# controller.net
KiCad netlist of a schematic drawn in EAGLE
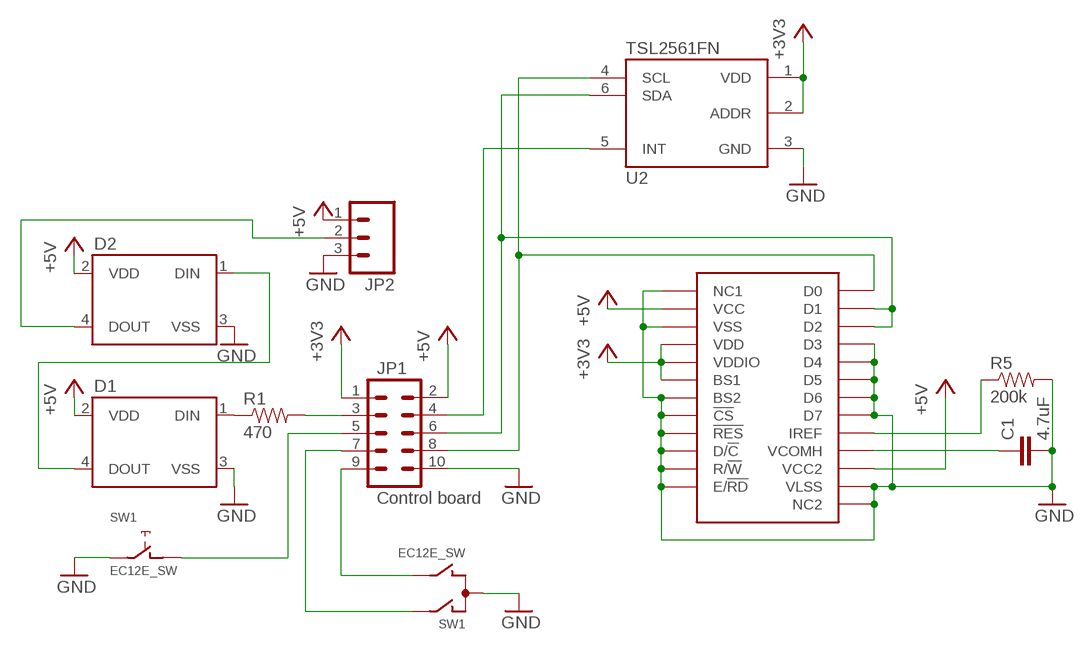
[diagram p0: schematic, sheet 1]

(export (version "E")
  (design (tool "Eeschema 10.0.6"))
  (components
    (comp (ref "C1")
      (value "4.7uF")
      (footprint "eagle-import:1206-CAP")
      (libsource (lib "eagle-import") (part "4.7UF-16V-20%,+80%-(1206)"))
    )
    (comp (ref "D1")
      (value "WS2812BTHRU")
      (footprint "eagle-import:APA-106-F5")
      (libsource (lib "eagle-import") (part "WS2812BTHRU"))
    )
    (comp (ref "D2")
      (value "WS2812BTHRU")
      (footprint "eagle-import:APA-106-F5")
      (libsource (lib "eagle-import") (part "WS2812BTHRU"))
    )
    (comp (ref "JP1")
      (value "Control board")
      (footprint "eagle-import:2X5-SHROUDED_LOCK")
      (libsource (lib "eagle-import") (part "M05X2SHD_LOCK"))
    )
    (comp (ref "JP2")
      (value "M03LOCK")
      (footprint "eagle-import:1X03_LOCK")
      (libsource (lib "eagle-import") (part "M03LOCK"))
    )
    (comp (ref "R1")
      (value "470")
      (footprint "eagle-import:0603-RES")
      (libsource (lib "eagle-import") (part "470OHM1/10W1%(0603)"))
    )
    (comp (ref "R5")
      (value "200k")
      (footprint "eagle-import:0603-RES")
      (libsource (lib "eagle-import") (part "300KOHM-1/10W-1%(0603)"))
    )
    (comp (ref "SW1")
      (value "EC12E_SW")
      (footprint "eagle-import:ALPS_EC12E_SW")
      (fields (field (name "MPN") "EC12E2424407"))
      (libsource (lib "eagle-import") (part "EC12E_SW"))
    )
    (comp (ref "U$1")
      (value "ER-OLED011")
      (footprint "eagle-import:ER-OLED011")
      (libsource (lib "eagle-import") (part "ER-OLED011"))
    )
    (comp (ref "U2")
      (value "TSL2561FN")
      (footprint "eagle-import:FN-6")
      (libsource (lib "eagle-import") (part "TSL2561FN"))
    )
  )
  (nets
    (net (code "1") (name "+3V3") (class "Default")
      (node (ref "JP1") (pin "1") (pinfunction "1_1") (pintype "passive"))
      (node (ref "U$1") (pin "BS1") (pinfunction "BS1_BS1") (pintype "bidirectional"))
      (node (ref "U$1") (pin "VDD") (pinfunction "VDD_VDD") (pintype "bidirectional"))
      (node (ref "U$1") (pin "VDDIO") (pinfunction "VDDIO_VDDIO") (pintype "bidirectional"))
      (node (ref "U2") (pin "1") (pinfunction "VDD_1") (pintype "power_in"))
      (node (ref "U2") (pin "2") (pinfunction "ADDR_2") (pintype "input"))
    )
    (net (code "2") (name "+5V") (class "Default")
      (node (ref "D1") (pin "2") (pinfunction "VDD_2") (pintype "power_in"))
      (node (ref "D2") (pin "2") (pinfunction "VDD_2") (pintype "power_in"))
      (node (ref "JP1") (pin "2") (pinfunction "2_2") (pintype "passive"))
      (node (ref "JP2") (pin "1") (pinfunction "1_1") (pintype "passive"))
      (node (ref "U$1") (pin "VCC") (pinfunction "VCC_VCC") (pintype "bidirectional"))
      (node (ref "U$1") (pin "VCC2") (pinfunction "VCC2_VCC2") (pintype "bidirectional"))
    )
    (net (code "3") (name "GND") (class "Default")
      (node (ref "C1") (pin "2") (pinfunction "2_2") (pintype "passive"))
      (node (ref "D1") (pin "3") (pinfunction "VSS_3") (pintype "power_in"))
      (node (ref "D2") (pin "3") (pinfunction "VSS_3") (pintype "power_in"))
      (node (ref "JP1") (pin "10") (pinfunction "10_10") (pintype "passive"))
      (node (ref "JP2") (pin "3") (pinfunction "3_3") (pintype "passive"))
      (node (ref "R5") (pin "2") (pinfunction "2_2") (pintype "passive"))
      (node (ref "SW1") (pin "C") (pinfunction "C_C") (pintype "passive"))
      (node (ref "SW1") (pin "E") (pinfunction "2_E") (pintype "passive"))
      (node (ref "U$1") (pin "!CS") (pinfunction "~{CS}_!CS") (pintype "bidirectional"))
      (node (ref "U$1") (pin "!RES") (pinfunction "~{RES}_!RES") (pintype "bidirectional"))
      (node (ref "U$1") (pin "BS2") (pinfunction "BS2_BS2") (pintype "bidirectional"))
      (node (ref "U$1") (pin "D/!C") (pinfunction "D/~{C}_D/!C") (pintype "bidirectional"))
      (node (ref "U$1") (pin "D3") (pinfunction "D3_D3") (pintype "bidirectional"))
      (node (ref "U$1") (pin "D4") (pinfunction "D4_D4") (pintype "bidirectional"))
      (node (ref "U$1") (pin "D5") (pinfunction "D5_D5") (pintype "bidirectional"))
      (node (ref "U$1") (pin "D6") (pinfunction "D6_D6") (pintype "bidirectional"))
      (node (ref "U$1") (pin "D7") (pinfunction "D7_D7") (pintype "bidirectional"))
      (node (ref "U$1") (pin "E/!RD") (pinfunction "E/~{RD}_E/!RD") (pintype "bidirectional"))
      (node (ref "U$1") (pin "NC1") (pinfunction "NC1_NC1") (pintype "bidirectional"))
      (node (ref "U$1") (pin "NC2") (pinfunction "NC2_NC2") (pintype "bidirectional"))
      (node (ref "U$1") (pin "R/!W") (pinfunction "R/~{W}_R/!W") (pintype "bidirectional"))
      (node (ref "U$1") (pin "VLSS") (pinfunction "VLSS_VLSS") (pintype "bidirectional"))
      (node (ref "U$1") (pin "VSS") (pinfunction "VSS_VSS") (pintype "bidirectional"))
      (node (ref "U2") (pin "3") (pinfunction "GND_3") (pintype "power_in"))
    )
    (net (code "4") (name "Net-(C1-Pad1)") (class "Default")
      (node (ref "C1") (pin "1") (pinfunction "1_1") (pintype "passive"))
      (node (ref "U$1") (pin "VCOMH") (pinfunction "VCOMH_VCOMH") (pintype "bidirectional"))
    )
    (net (code "5") (name "Net-(D1-DIN)") (class "Default")
      (node (ref "D1") (pin "1") (pinfunction "DIN_1") (pintype "input"))
      (node (ref "R1") (pin "1") (pinfunction "1_1") (pintype "passive"))
    )
    (net (code "6") (name "Net-(D1-DOUT)") (class "Default")
      (node (ref "D1") (pin "4") (pinfunction "DOUT_4") (pintype "output"))
      (node (ref "D2") (pin "1") (pinfunction "DIN_1") (pintype "input"))
    )
    (net (code "7") (name "Net-(D2-DOUT)") (class "Default")
      (node (ref "D2") (pin "4") (pinfunction "DOUT_4") (pintype "output"))
      (node (ref "JP2") (pin "2") (pinfunction "2_2") (pintype "passive"))
    )
    (net (code "8") (name "Net-(JP1-Pad3)") (class "Default")
      (node (ref "JP1") (pin "3") (pinfunction "3_3") (pintype "passive"))
      (node (ref "R1") (pin "2") (pinfunction "2_2") (pintype "passive"))
    )
    (net (code "9") (name "Net-(JP1-Pad7)") (class "Default")
      (node (ref "JP1") (pin "7") (pinfunction "7_7") (pintype "passive"))
      (node (ref "SW1") (pin "A") (pinfunction "A_A") (pintype "passive"))
    )
    (net (code "10") (name "Net-(JP1-Pad9)") (class "Default")
      (node (ref "JP1") (pin "9") (pinfunction "9_9") (pintype "passive"))
      (node (ref "SW1") (pin "B") (pinfunction "B_B") (pintype "passive"))
    )
    (net (code "11") (name "Net-(R5-Pad1)") (class "Default")
      (node (ref "R5") (pin "1") (pinfunction "1_1") (pintype "passive"))
      (node (ref "U$1") (pin "IREF") (pinfunction "IREF_IREF") (pintype "bidirectional"))
    )
    (net (code "12") (name "Net-(SW1B-1)") (class "Default")
      (node (ref "JP1") (pin "5") (pinfunction "5_5") (pintype "passive"))
      (node (ref "SW1") (pin "D") (pinfunction "1_D") (pintype "passive"))
    )
    (net (code "13") (name "Net-(U2-INT)") (class "Default")
      (node (ref "JP1") (pin "4") (pinfunction "4_4") (pintype "passive"))
      (node (ref "U2") (pin "5") (pinfunction "INT_5") (pintype "output"))
    )
    (net (code "14") (name "Net-(U2-SCL)") (class "Default")
      (node (ref "JP1") (pin "8") (pinfunction "8_8") (pintype "passive"))
      (node (ref "U$1") (pin "D0") (pinfunction "D0_D0") (pintype "bidirectional"))
      (node (ref "U2") (pin "4") (pinfunction "SCL_4") (pintype "input"))
    )
    (net (code "15") (name "Net-(U2-SDA)") (class "Default")
      (node (ref "JP1") (pin "6") (pinfunction "6_6") (pintype "passive"))
      (node (ref "U$1") (pin "D1") (pinfunction "D1_D1") (pintype "bidirectional"))
      (node (ref "U$1") (pin "D2") (pinfunction "D2_D2") (pintype "bidirectional"))
      (node (ref "U2") (pin "6") (pinfunction "SDA_6") (pintype "bidirectional"))
    )
  )
)
